# LAUNCHPAD.net
KiCad netlist of a schematic drawn in Altium Designer
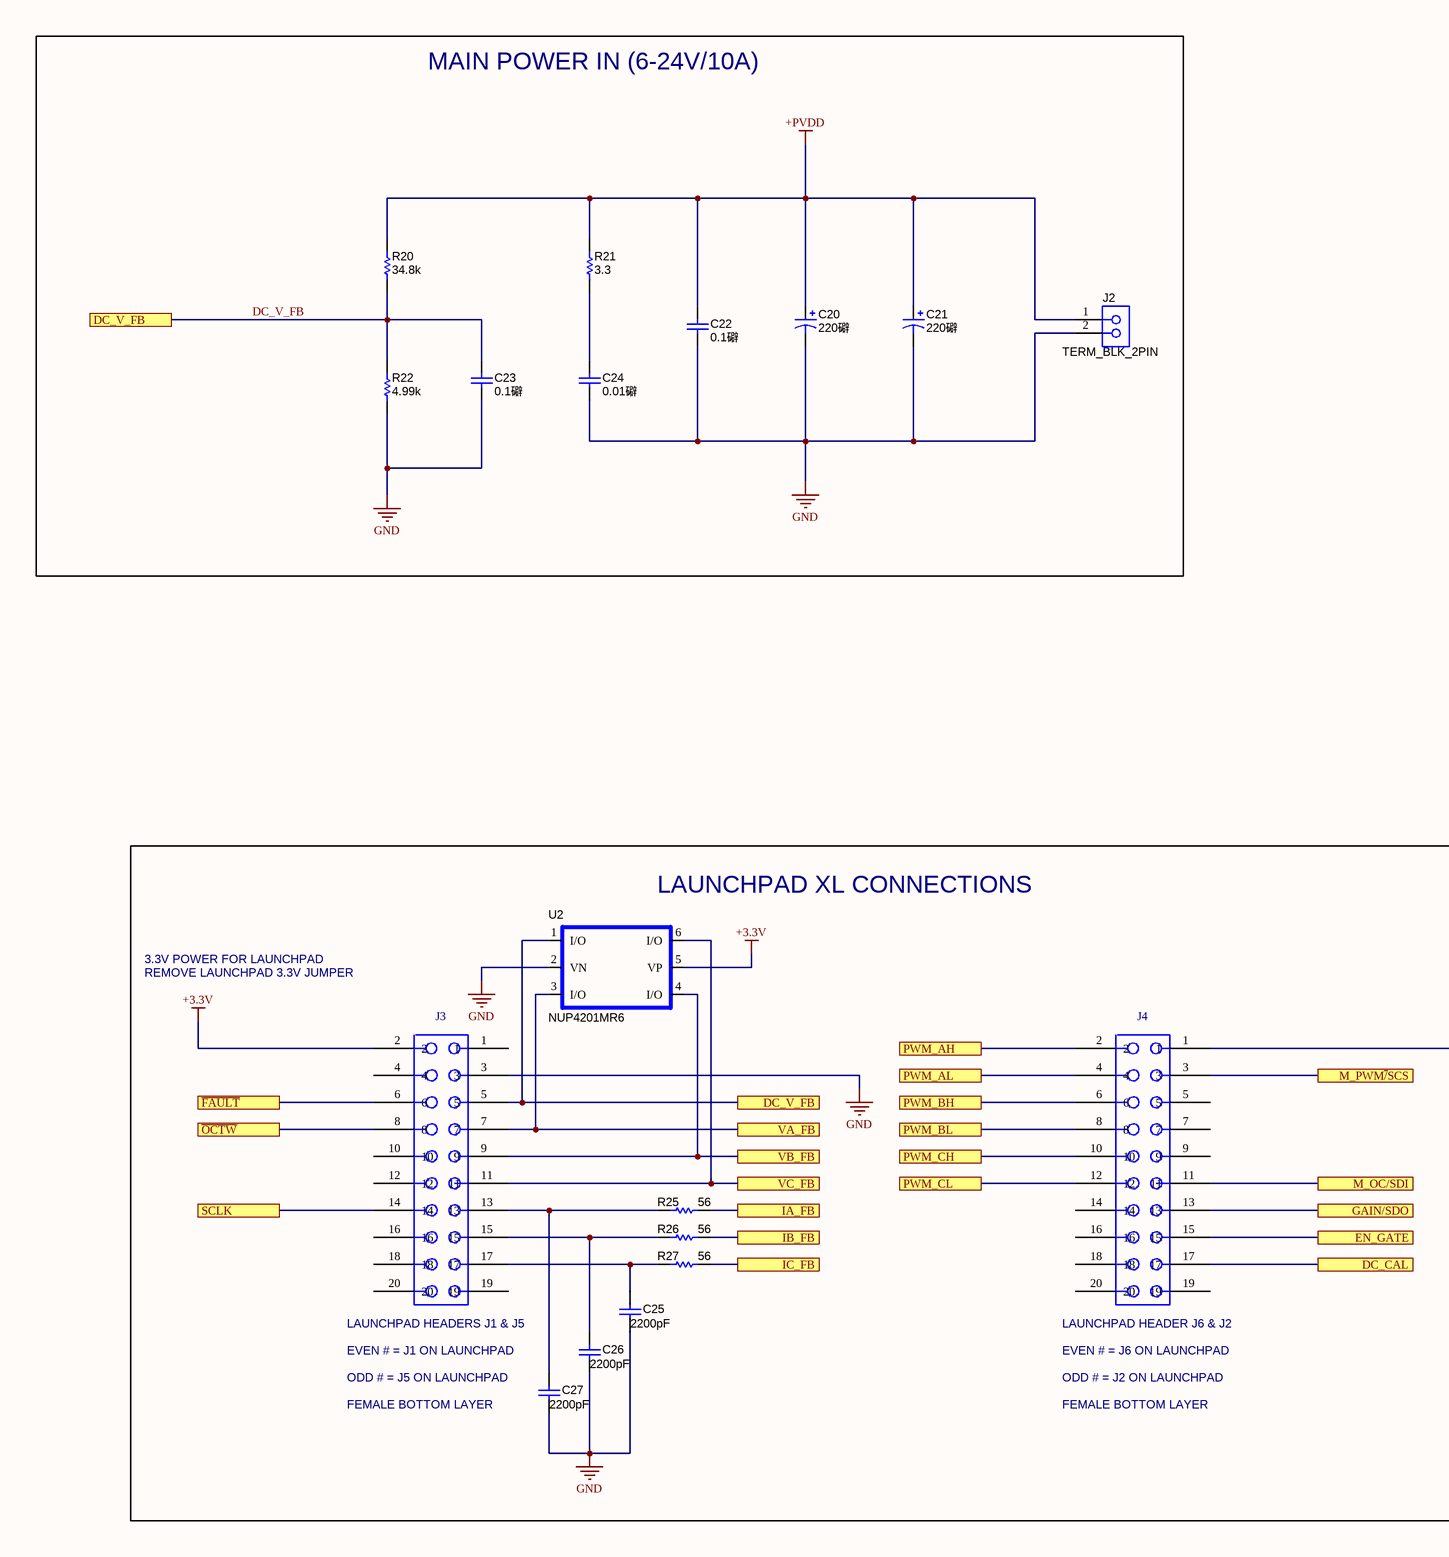
[diagram p0: LAUNCHPAD.SchDoc, left]
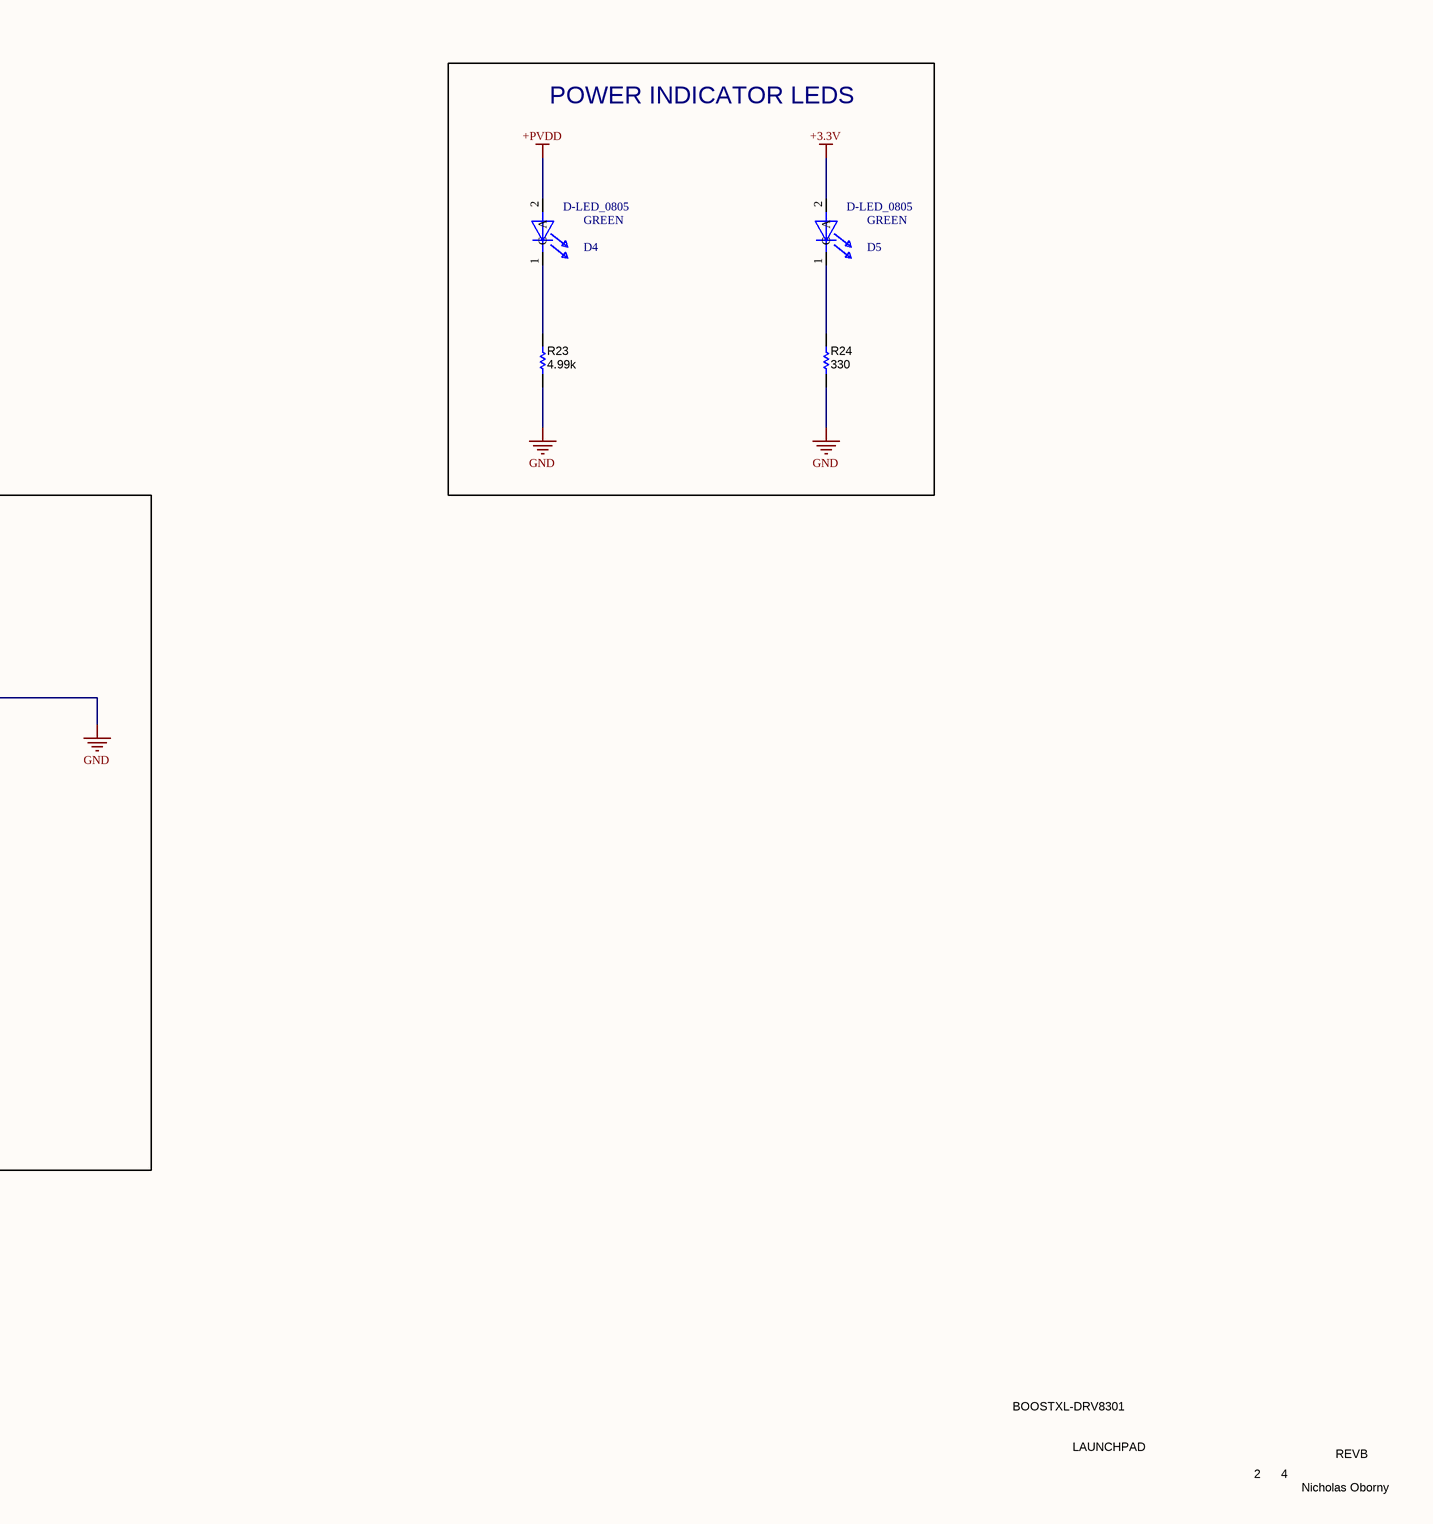
[diagram p1: LAUNCHPAD.SchDoc, right]

(export (version "E")
  (design (tool "Eeschema 10.0.6"))
  (components
    (comp (ref "C20")
      (value "EEE-FC1H221P")
      (footprint "SM_RADIAL_G")
      (description "CAP, AL, 220uF, 50V, +/-20%, 0.3 ohm, SMD")
      (fields
        (field (name "VALUEDISPLAYED") "220礔")
        (field (name "MANUFACTURER") "Panasonic")
        (field (name "PUBLISHER") "Texas Instruments")
      )
      (libsource (lib "Capacitor_Aluminum") (part "EEE-FC1H221P"))
    )
    (comp (ref "C21")
      (value "EEE-FC1H221P")
      (footprint "SM_RADIAL_G")
      (description "CAP, AL, 220uF, 50V, +/-20%, 0.3 ohm, SMD")
      (fields
        (field (name "VALUEDISPLAYED") "220礔")
        (field (name "MANUFACTURER") "Panasonic")
        (field (name "PUBLISHER") "Texas Instruments")
      )
      (libsource (lib "Capacitor_Aluminum") (part "EEE-FC1H221P"))
    )
    (comp (ref "C22")
      (value "GRM188R72A104KA35D")
      (footprint "0603L")
      (description "CAP, CERM, 0.1uF, 100V, +/-10%, X7R, 0603")
      (fields
        (field (name "VALUEDISPLAYED") "0.1礔")
        (field (name "MANUFACTURER") "MuRata")
        (field (name "PUBLISHER") "Texas Instruments")
      )
      (libsource (lib "Capacitor_Ceramic") (part "GRM188R72A104KA35D"))
    )
    (comp (ref "C23")
      (value "C0603C104J4RACTU")
      (footprint "0603L")
      (description "CAP, CERM, 0.1uF, 16V, +/-5%, X7R, 0603")
      (fields
        (field (name "VALUEDISPLAYED") "0.1礔")
        (field (name "MANUFACTURER") "Kemet")
        (field (name "PUBLISHER") "Texas Instruments")
      )
      (libsource (lib "Capacitor_Ceramic") (part "C0603C104J4RACTU"))
    )
    (comp (ref "C24")
      (value "C1608X7R2A103K")
      (footprint "0603L")
      (description "CAP, CERM, 0.01uF, 100V, +/-10%, X7R, 0603")
      (fields
        (field (name "VALUEDISPLAYED") "0.01礔")
        (field (name "MANUFACTURER") "TDK")
        (field (name "PUBLISHER") "Texas Instruments")
      )
      (libsource (lib "Capacitor_Ceramic") (part "C1608X7R2A103K"))
    )
    (comp (ref "C25")
      (value "GRM188R71C222KA01D")
      (footprint "0603L")
      (description "CAP, CERM, 2200pF, 16V, +/-10%, X7R, 0603")
      (fields
        (field (name "VALUEDISPLAYED") "2200pF")
        (field (name "MANUFACTURER") "MuRata")
        (field (name "PUBLISHER") "Texas Instruments")
      )
      (libsource (lib "Capacitor_Ceramic") (part "GRM188R71C222KA01D"))
    )
    (comp (ref "C26")
      (value "GRM188R71C222KA01D")
      (footprint "0603L")
      (description "CAP, CERM, 2200pF, 16V, +/-10%, X7R, 0603")
      (fields
        (field (name "VALUEDISPLAYED") "2200pF")
        (field (name "MANUFACTURER") "MuRata")
        (field (name "PUBLISHER") "Texas Instruments")
      )
      (libsource (lib "Capacitor_Ceramic") (part "GRM188R71C222KA01D"))
    )
    (comp (ref "C27")
      (value "GRM188R71C222KA01D")
      (footprint "0603L")
      (description "CAP, CERM, 2200pF, 16V, +/-10%, X7R, 0603")
      (fields
        (field (name "VALUEDISPLAYED") "2200pF")
        (field (name "MANUFACTURER") "MuRata")
        (field (name "PUBLISHER") "Texas Instruments")
      )
      (libsource (lib "Capacitor_Ceramic") (part "GRM188R71C222KA01D"))
    )
    (comp (ref "D4")
      (value "D-LED_0805")
      (footprint "LED_0805")
      (description "LED THIN 565NM GRN DIFF 0805 SMD")
      (fields
        (field (name "PARTNUMBER") "SML-LXT0805GW-TR")
        (field (name "ALTIUM_VALUE") "GREEN")
        (field (name "MANUFACTURER") "Lumex Opto/Components Inc")
      )
      (libsource (lib "*") (part "D-LED_0805"))
    )
    (comp (ref "D5")
      (value "D-LED_0805")
      (footprint "LED_0805")
      (description "LED THIN 565NM GRN DIFF 0805 SMD")
      (fields
        (field (name "PARTNUMBER") "SML-LXT0805GW-TR")
        (field (name "ALTIUM_VALUE") "GREEN")
        (field (name "MANUFACTURER") "Lumex Opto/Components Inc")
      )
      (libsource (lib "*") (part "D-LED_0805"))
    )
    (comp (ref "J2")
      (value "TERM_BLK_2PIN")
      (footprint "CONN_ED120-2DS")
      (description "TERMINAL BLOCK 5.08MM VERT 2POS")
      (fields
        (field (name "PARTNUMBER") "OSTTA024163")
        (field (name "MANUFACTURER") "On-Shore Technology")
        (field (name "PUBLISHER") "Texas Instruments")
      )
      (libsource (lib "Connectors") (part "ED120/2DS"))
    )
    (comp (ref "J3")
      (value "HEADER_NPTC202KFM")
      (description "CONN RCPT 20POS .100 DL STR SMD")
      (fields (field (name "PARTNUMBER") "89898-310ALF") (field (name "MANUFACTURER") "FCI"))
      (libsource (lib "*") (part "HEADER_NPTC202KFM"))
    )
    (comp (ref "J4")
      (value "HEADER_NPTC202KFM")
      (description "CONN RCPT 20POS .100 DL STR SMD")
      (fields (field (name "PARTNUMBER") "89898-310ALF") (field (name "MANUFACTURER") "FCI"))
      (libsource (lib "*") (part "HEADER_NPTC202KFM"))
    )
    (comp (ref "R20")
      (value "34.8k")
      (footprint "0603L")
      (description "RES, 34.8k ohm, 1%, 0.1W, 0603")
      (fields
        (field (name "PARTNUMBER") "CRCW060334K8FKEA")
        (field (name "MANUFACTURER") "Vishay-Dale")
        (field (name "PUBLISHER") "Texas Instruments")
      )
      (libsource (lib "Resistor_0603") (part "CRCW060334K8FKEA"))
    )
    (comp (ref "R21")
      (value "3.3")
      (footprint "1206L")
      (description "RES, 3.3 ohm, 5%, 0.25W, 1206")
      (fields
        (field (name "PARTNUMBER") "CRCW12063R30JNEA")
        (field (name "MANUFACTURER") "Vishay-Dale")
        (field (name "PUBLISHER") "Texas Instruments")
      )
      (libsource (lib "Resistor_1206") (part "CRCW12063R30JNEA"))
    )
    (comp (ref "R22")
      (value "4.99k")
      (footprint "0603L")
      (description "RES, 4.99k ohm, 1%, 0.1W, 0603")
      (fields
        (field (name "PARTNUMBER") "CRCW06034K99FKEA")
        (field (name "MANUFACTURER") "Vishay-Dale")
        (field (name "PUBLISHER") "Texas Instruments")
      )
      (libsource (lib "Resistor_0603") (part "CRCW06034K99FKEA"))
    )
    (comp (ref "R23")
      (value "4.99k")
      (footprint "0603L")
      (description "RES, 4.99k ohm, 1%, 0.1W, 0603")
      (fields
        (field (name "PARTNUMBER") "CRCW06034K99FKEA")
        (field (name "MANUFACTURER") "Vishay-Dale")
        (field (name "PUBLISHER") "Texas Instruments")
      )
      (libsource (lib "Resistor_0603") (part "CRCW06034K99FKEA"))
    )
    (comp (ref "R24")
      (value "330")
      (footprint "0603L")
      (description "RES, 330 ohm, 5%, 0.1W, 0603")
      (fields
        (field (name "PARTNUMBER") "CRCW0603330RJNEA")
        (field (name "MANUFACTURER") "Vishay-Dale")
        (field (name "PUBLISHER") "Texas Instruments")
      )
      (libsource (lib "Resistor_0603") (part "CRCW0603330RJNEA"))
    )
    (comp (ref "R25")
      (value "56")
      (footprint "0603L")
      (description "RES, 56 ohm, 5%, 0.1W, 0603")
      (fields
        (field (name "PARTNUMBER") "CRCW060356R0JNEA")
        (field (name "MANUFACTURER") "Vishay-Dale")
        (field (name "PUBLISHER") "Texas Instruments")
      )
      (libsource (lib "Resistor_0603") (part "CRCW060356R0JNEA"))
    )
    (comp (ref "R26")
      (value "56")
      (footprint "0603L")
      (description "RES, 56 ohm, 5%, 0.1W, 0603")
      (fields
        (field (name "PARTNUMBER") "CRCW060356R0JNEA")
        (field (name "MANUFACTURER") "Vishay-Dale")
        (field (name "PUBLISHER") "Texas Instruments")
      )
      (libsource (lib "Resistor_0603") (part "CRCW060356R0JNEA"))
    )
    (comp (ref "R27")
      (value "56")
      (footprint "0603L")
      (description "RES, 56 ohm, 5%, 0.1W, 0603")
      (fields
        (field (name "PARTNUMBER") "CRCW060356R0JNEA")
        (field (name "MANUFACTURER") "Vishay-Dale")
        (field (name "PUBLISHER") "Texas Instruments")
      )
      (libsource (lib "Resistor_0603") (part "CRCW060356R0JNEA"))
    )
    (comp (ref "U2")
      (value "NUP4201MR6")
      (footprint "SOT23-6")
      (description "IC,  500w 6v, Transient Voltage  Suppressors")
      (fields (field (name "MANUFACTURER") "On Semi"))
      (libsource (lib "PADSlegacy_PMP") (part "NUP4201MR6"))
    )
  )
  (nets
    (net (code "1") (name "+3.3V") (class "Default")
      (node (ref "D5") (pin "2") (pinfunction "A_2") (pintype "passive"))
      (node (ref "J3") (pin "2") (pinfunction "2_2") (pintype "passive"))
      (node (ref "U2") (pin "5") (pinfunction "VP_5") (pintype "passive"))
    )
    (net (code "2") (name "+PVDD") (class "Default")
      (node (ref "C20") (pin "1") (pinfunction "+_1") (pintype "passive"))
      (node (ref "C21") (pin "1") (pinfunction "+_1") (pintype "passive"))
      (node (ref "C22") (pin "1") (pinfunction "1_1") (pintype "passive"))
      (node (ref "D4") (pin "2") (pinfunction "A_2") (pintype "passive"))
      (node (ref "J2") (pin "1") (pinfunction "1_1") (pintype "passive"))
      (node (ref "R20") (pin "2") (pinfunction "2_2") (pintype "passive"))
      (node (ref "R21") (pin "2") (pinfunction "2_2") (pintype "passive"))
    )
    (net (code "3") (name "/DC_CAL") (class "Default")
      (node (ref "J4") (pin "17") (pinfunction "17_17") (pintype "passive"))
    )
    (net (code "4") (name "/DC_V_FB") (class "Default")
      (node (ref "C23") (pin "1") (pinfunction "1_1") (pintype "passive"))
      (node (ref "J3") (pin "5") (pinfunction "5_5") (pintype "passive"))
      (node (ref "R20") (pin "1") (pinfunction "1_1") (pintype "passive"))
      (node (ref "R22") (pin "2") (pinfunction "2_2") (pintype "passive"))
      (node (ref "U2") (pin "1") (pinfunction "I/O_1") (pintype "passive"))
    )
    (net (code "5") (name "/EN_GATE") (class "Default")
      (node (ref "J4") (pin "15") (pinfunction "15_15") (pintype "passive"))
    )
    (net (code "6") (name "/FAULT") (class "Default")
      (node (ref "J3") (pin "6") (pinfunction "6_6") (pintype "passive"))
    )
    (net (code "7") (name "/GAIN{slash}SDO") (class "Default")
      (node (ref "J4") (pin "13") (pinfunction "13_13") (pintype "passive"))
    )
    (net (code "8") (name "/IA_FB") (class "Default")
      (node (ref "R25") (pin "2") (pinfunction "2_2") (pintype "passive"))
    )
    (net (code "9") (name "/IB_FB") (class "Default")
      (node (ref "R26") (pin "2") (pinfunction "2_2") (pintype "passive"))
    )
    (net (code "10") (name "/IC_FB") (class "Default")
      (node (ref "R27") (pin "2") (pinfunction "2_2") (pintype "passive"))
    )
    (net (code "11") (name "/M_OC{slash}SDI") (class "Default")
      (node (ref "J4") (pin "11") (pinfunction "11_11") (pintype "passive"))
    )
    (net (code "12") (name "/M_PWM~{{slash}}SCS") (class "Default")
      (node (ref "J4") (pin "3") (pinfunction "3_3") (pintype "passive"))
    )
    (net (code "13") (name "/OCTW") (class "Default")
      (node (ref "J3") (pin "8") (pinfunction "8_8") (pintype "passive"))
    )
    (net (code "14") (name "/PWM_AH") (class "Default")
      (node (ref "J4") (pin "2") (pinfunction "2_2") (pintype "passive"))
    )
    (net (code "15") (name "/PWM_AL") (class "Default")
      (node (ref "J4") (pin "4") (pinfunction "4_4") (pintype "passive"))
    )
    (net (code "16") (name "/PWM_BH") (class "Default")
      (node (ref "J4") (pin "6") (pinfunction "6_6") (pintype "passive"))
    )
    (net (code "17") (name "/PWM_BL") (class "Default")
      (node (ref "J4") (pin "8") (pinfunction "8_8") (pintype "passive"))
    )
    (net (code "18") (name "/PWM_CH") (class "Default")
      (node (ref "J4") (pin "10") (pinfunction "10_10") (pintype "passive"))
    )
    (net (code "19") (name "/PWM_CL") (class "Default")
      (node (ref "J4") (pin "12") (pinfunction "12_12") (pintype "passive"))
    )
    (net (code "20") (name "/SCLK") (class "Default")
      (node (ref "J3") (pin "14") (pinfunction "14_14") (pintype "passive"))
    )
    (net (code "21") (name "/VA_FB") (class "Default")
      (node (ref "J3") (pin "7") (pinfunction "7_7") (pintype "passive"))
      (node (ref "U2") (pin "3") (pinfunction "I/O_3") (pintype "passive"))
    )
    (net (code "22") (name "/VB_FB") (class "Default")
      (node (ref "J3") (pin "9") (pinfunction "9_9") (pintype "passive"))
      (node (ref "U2") (pin "4") (pinfunction "I/O_4") (pintype "passive"))
    )
    (net (code "23") (name "/VC_FB") (class "Default")
      (node (ref "J3") (pin "11") (pinfunction "11_11") (pintype "passive"))
      (node (ref "U2") (pin "6") (pinfunction "I/O_6") (pintype "passive"))
    )
    (net (code "24") (name "GND") (class "Default")
      (node (ref "C20") (pin "2") (pinfunction "-_2") (pintype "passive"))
      (node (ref "C21") (pin "2") (pinfunction "-_2") (pintype "passive"))
      (node (ref "C22") (pin "2") (pinfunction "2_2") (pintype "passive"))
      (node (ref "C23") (pin "2") (pinfunction "2_2") (pintype "passive"))
      (node (ref "C24") (pin "2") (pinfunction "2_2") (pintype "passive"))
      (node (ref "C25") (pin "2") (pinfunction "2_2") (pintype "passive"))
      (node (ref "C26") (pin "2") (pinfunction "2_2") (pintype "passive"))
      (node (ref "C27") (pin "2") (pinfunction "2_2") (pintype "passive"))
      (node (ref "J2") (pin "2") (pinfunction "2_2") (pintype "passive"))
      (node (ref "J3") (pin "3") (pinfunction "3_3") (pintype "passive"))
      (node (ref "J4") (pin "1") (pinfunction "1_1") (pintype "passive"))
      (node (ref "R22") (pin "1") (pinfunction "1_1") (pintype "passive"))
      (node (ref "R23") (pin "1") (pinfunction "1_1") (pintype "passive"))
      (node (ref "R24") (pin "1") (pinfunction "1_1") (pintype "passive"))
      (node (ref "U2") (pin "2") (pinfunction "VN_2") (pintype "passive"))
    )
    (net (code "25") (name "Net-(C24-Pad1)") (class "Default")
      (node (ref "C24") (pin "1") (pinfunction "1_1") (pintype "passive"))
      (node (ref "R21") (pin "1") (pinfunction "1_1") (pintype "passive"))
    )
    (net (code "26") (name "Net-(C25-Pad1)") (class "Default")
      (node (ref "C25") (pin "1") (pinfunction "1_1") (pintype "passive"))
      (node (ref "J3") (pin "17") (pinfunction "17_17") (pintype "passive"))
      (node (ref "R27") (pin "1") (pinfunction "1_1") (pintype "passive"))
    )
    (net (code "27") (name "Net-(C26-Pad1)") (class "Default")
      (node (ref "C26") (pin "1") (pinfunction "1_1") (pintype "passive"))
      (node (ref "J3") (pin "15") (pinfunction "15_15") (pintype "passive"))
      (node (ref "R26") (pin "1") (pinfunction "1_1") (pintype "passive"))
    )
    (net (code "28") (name "Net-(C27-Pad1)") (class "Default")
      (node (ref "C27") (pin "1") (pinfunction "1_1") (pintype "passive"))
      (node (ref "J3") (pin "13") (pinfunction "13_13") (pintype "passive"))
      (node (ref "R25") (pin "1") (pinfunction "1_1") (pintype "passive"))
    )
    (net (code "29") (name "Net-(D4-C)") (class "Default")
      (node (ref "D4") (pin "1") (pinfunction "C_1") (pintype "passive"))
      (node (ref "R23") (pin "2") (pinfunction "2_2") (pintype "passive"))
    )
    (net (code "30") (name "Net-(D5-C)") (class "Default")
      (node (ref "D5") (pin "1") (pinfunction "C_1") (pintype "passive"))
      (node (ref "R24") (pin "2") (pinfunction "2_2") (pintype "passive"))
    )
    (net (code "31") (name "unconnected-(J3-Pad1)") (class "Default")
      (node (ref "J3") (pin "1") (pinfunction "1_1") (pintype "passive"))
    )
    (net (code "32") (name "unconnected-(J3-Pad4)") (class "Default")
      (node (ref "J3") (pin "4") (pinfunction "4_4") (pintype "passive"))
    )
    (net (code "33") (name "unconnected-(J3-Pad10)") (class "Default")
      (node (ref "J3") (pin "10") (pinfunction "10_10") (pintype "passive"))
    )
    (net (code "34") (name "unconnected-(J3-Pad12)") (class "Default")
      (node (ref "J3") (pin "12") (pinfunction "12_12") (pintype "passive"))
    )
    (net (code "35") (name "unconnected-(J3-Pad16)") (class "Default")
      (node (ref "J3") (pin "16") (pinfunction "16_16") (pintype "passive"))
    )
    (net (code "36") (name "unconnected-(J3-Pad18)") (class "Default")
      (node (ref "J3") (pin "18") (pinfunction "18_18") (pintype "passive"))
    )
    (net (code "37") (name "unconnected-(J3-Pad19)") (class "Default")
      (node (ref "J3") (pin "19") (pinfunction "19_19") (pintype "passive"))
    )
    (net (code "38") (name "unconnected-(J3-Pad20)") (class "Default")
      (node (ref "J3") (pin "20") (pinfunction "20_20") (pintype "passive"))
    )
    (net (code "39") (name "unconnected-(J4-Pad5)") (class "Default")
      (node (ref "J4") (pin "5") (pinfunction "5_5") (pintype "passive"))
    )
    (net (code "40") (name "unconnected-(J4-Pad7)") (class "Default")
      (node (ref "J4") (pin "7") (pinfunction "7_7") (pintype "passive"))
    )
    (net (code "41") (name "unconnected-(J4-Pad9)") (class "Default")
      (node (ref "J4") (pin "9") (pinfunction "9_9") (pintype "passive"))
    )
    (net (code "42") (name "unconnected-(J4-Pad14)") (class "Default")
      (node (ref "J4") (pin "14") (pinfunction "14_14") (pintype "passive"))
    )
    (net (code "43") (name "unconnected-(J4-Pad16)") (class "Default")
      (node (ref "J4") (pin "16") (pinfunction "16_16") (pintype "passive"))
    )
    (net (code "44") (name "unconnected-(J4-Pad18)") (class "Default")
      (node (ref "J4") (pin "18") (pinfunction "18_18") (pintype "passive"))
    )
    (net (code "45") (name "unconnected-(J4-Pad19)") (class "Default")
      (node (ref "J4") (pin "19") (pinfunction "19_19") (pintype "passive"))
    )
    (net (code "46") (name "unconnected-(J4-Pad20)") (class "Default")
      (node (ref "J4") (pin "20") (pinfunction "20_20") (pintype "passive"))
    )
  )
)
